# Microcontroller.net
KiCad netlist of a schematic drawn in Altium Designer
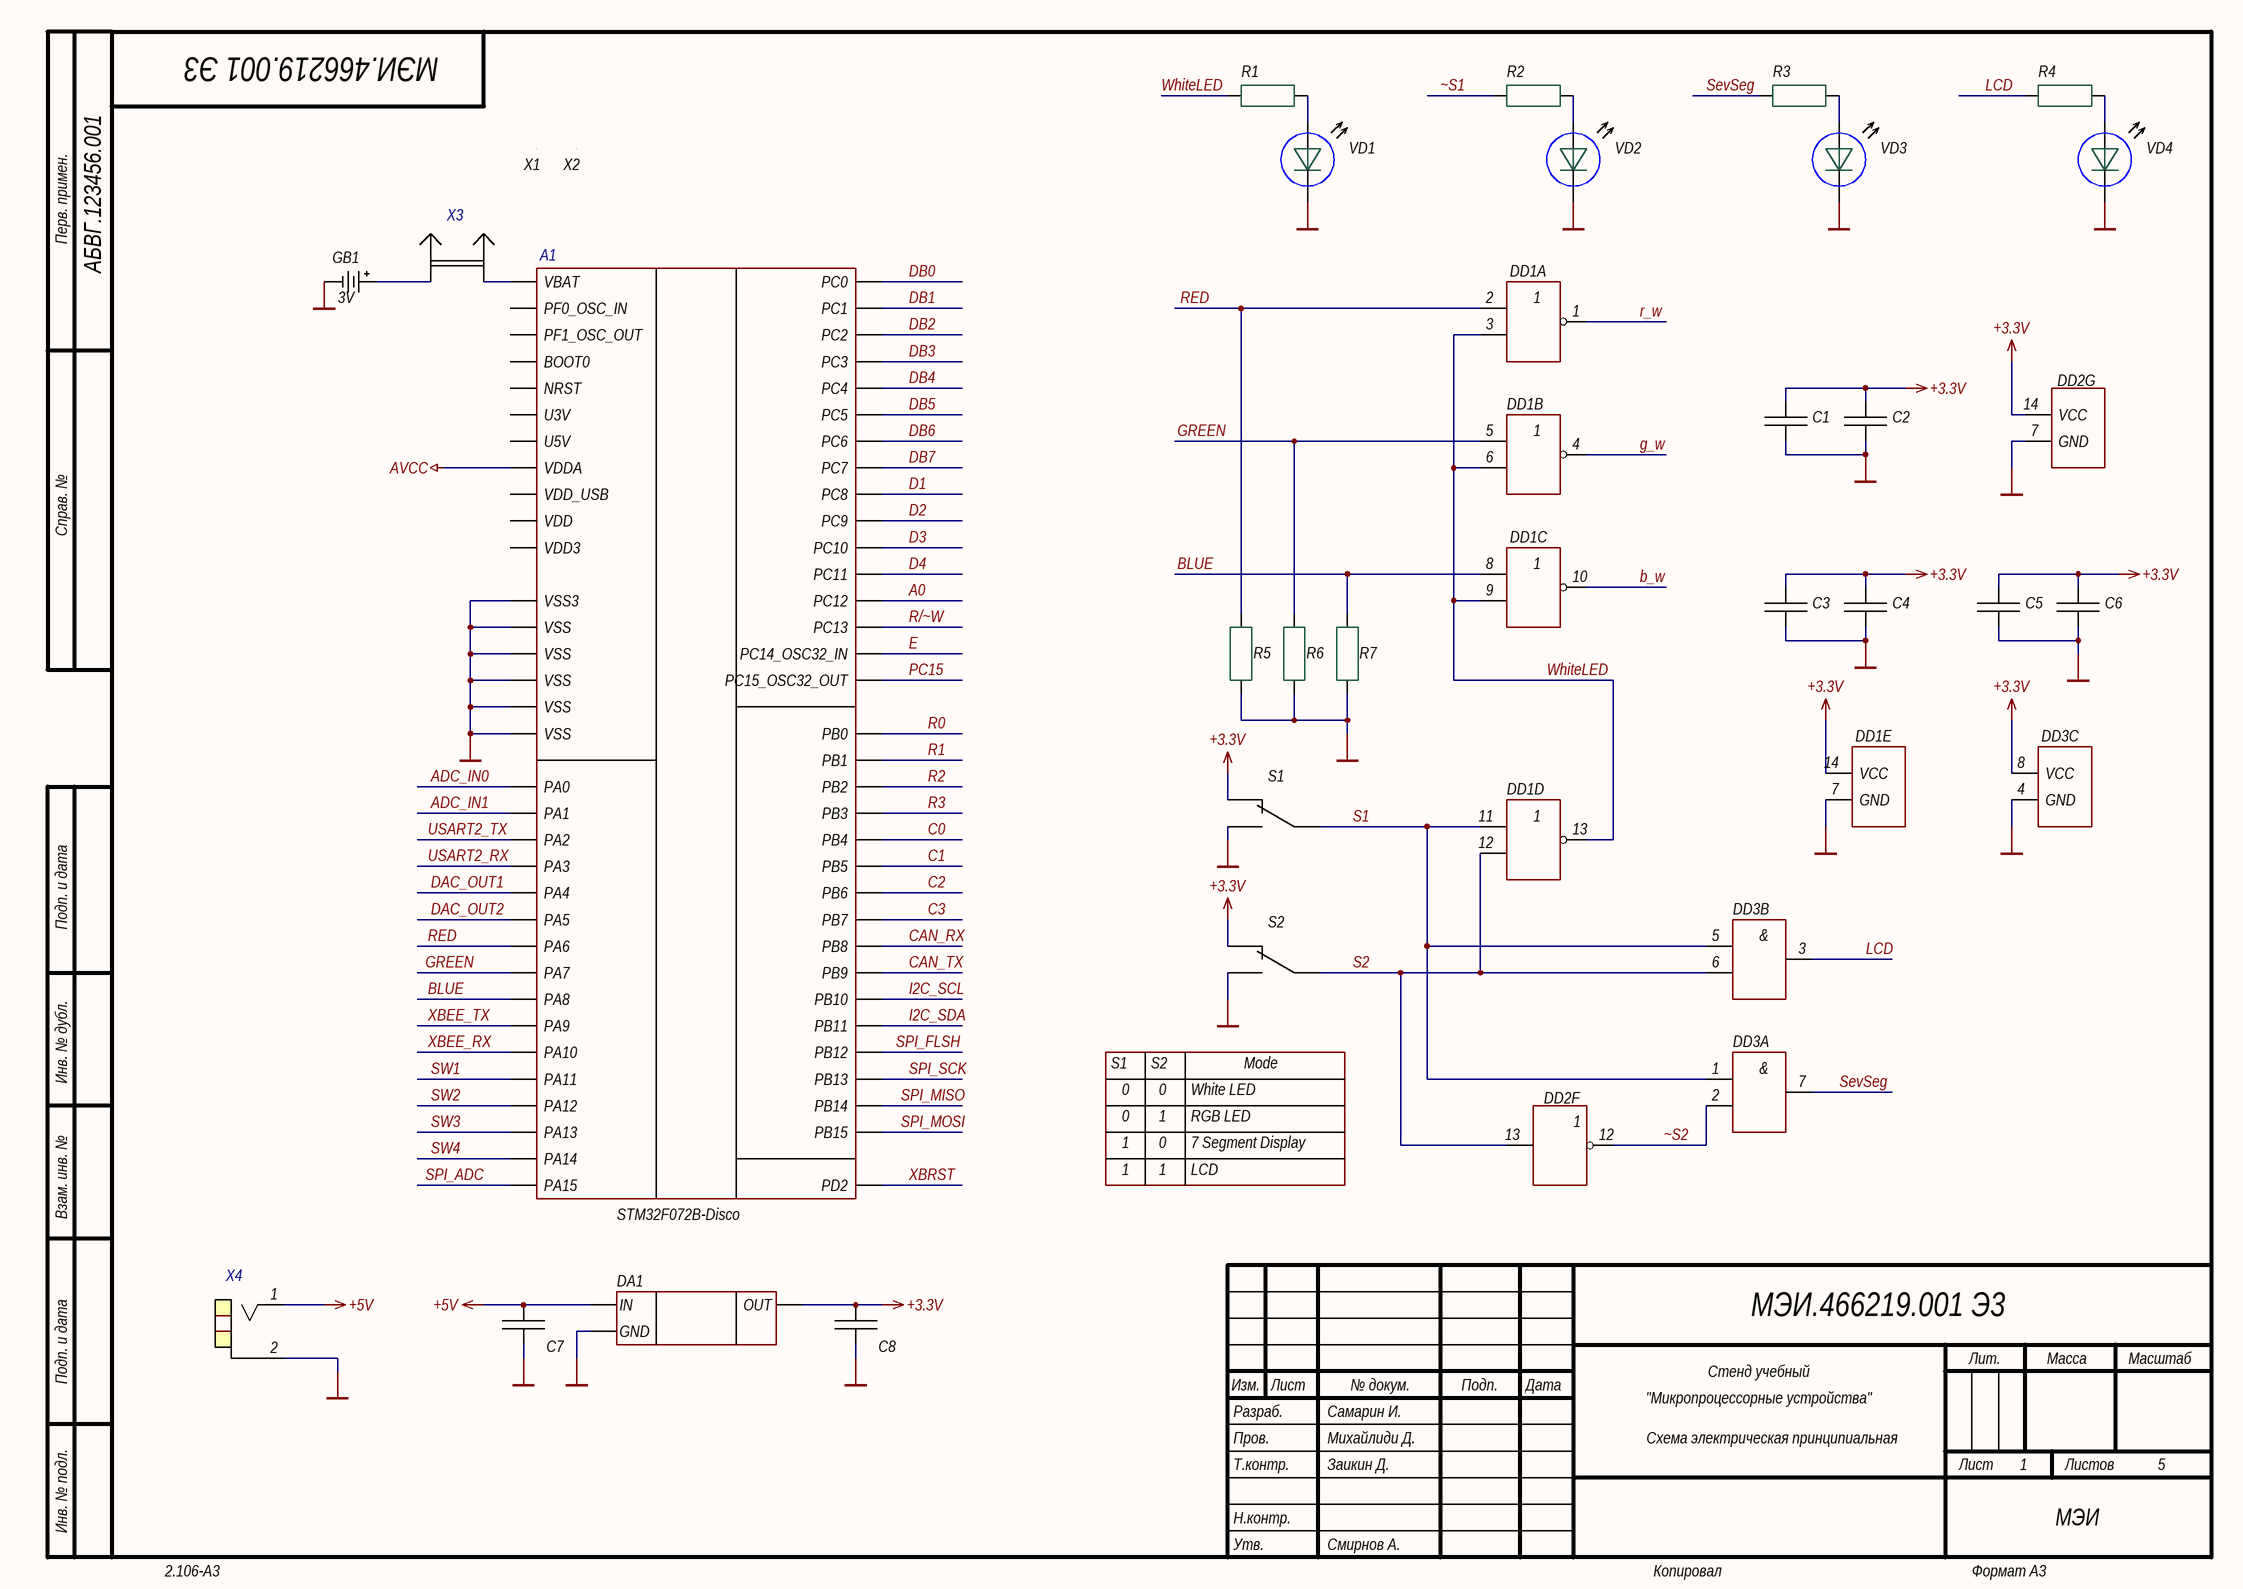
[diagram p0: Microcontroller.SchDoc]

(export (version "E")
  (design (tool "Eeschema 10.0.6"))
  (components
    (comp (ref "A1")
      (value "STM32F072B-Disco")
      (footprint "LeSta:STM32F072B-Disco")
      (description "The STM32F072 discovery kit")
      (fields (field (name "MODEL") "STM32F072B-Disco"))
      (libsource (lib "LeSta") (part "STM32F072B-Disco"))
    )
    (comp (ref "C1")
      (value "approved sub OK")
      (footprint "CAPC1608X90N")
      (description "Capacitor SMD Cer 100nF 10% 50V X7R 0603")
      (fields (field (name "TOLERANCE") "±10%"))
      (libsource (lib "PBL - Capacitors") (part "CAPC_100n_0603_X7R_50V_10%"))
    )
    (comp (ref "C2")
      (value "approved sub OK")
      (footprint "PBL - SMD Packages:CAPC1608X90N")
      (description "Capacitor SMD Cer 10uF 10% 10V X5R 0603")
      (fields (field (name "TOLERANCE") "±10%"))
      (libsource (lib "PBL - Capacitors") (part "CAPC_10u_0805_10V"))
    )
    (comp (ref "C3")
      (value "approved sub OK")
      (footprint "CAPC1608X90N")
      (description "Capacitor SMD Cer 100nF 10% 50V X7R 0603")
      (fields (field (name "TOLERANCE") "±10%"))
      (libsource (lib "PBL - Capacitors") (part "CAPC_100n_0603_X7R_50V_10%"))
    )
    (comp (ref "C4")
      (value "approved sub OK")
      (footprint "PBL - SMD Packages:CAPC1608X90N")
      (description "Capacitor SMD Cer 10uF 10% 10V X5R 0603")
      (fields (field (name "TOLERANCE") "±10%"))
      (libsource (lib "PBL - Capacitors") (part "CAPC_10u_0805_10V"))
    )
    (comp (ref "C5")
      (value "approved sub OK")
      (footprint "CAPC1608X90N")
      (description "Capacitor SMD Cer 100nF 10% 50V X7R 0603")
      (fields (field (name "TOLERANCE") "±10%"))
      (libsource (lib "PBL - Capacitors") (part "CAPC_100n_0603_X7R_50V_10%"))
    )
    (comp (ref "C6")
      (value "approved sub OK")
      (footprint "PBL - SMD Packages:CAPC1608X90N")
      (description "Capacitor SMD Cer 10uF 10% 10V X5R 0603")
      (fields (field (name "TOLERANCE") "±10%"))
      (libsource (lib "PBL - Capacitors") (part "CAPC_10u_0805_10V"))
    )
    (comp (ref "C7")
      (value "approved sub OK")
      (footprint "CAPC1608X90N")
      (description "Capacitor SMD Cer 1uF 10% 16V X7R 0603")
      (fields (field (name "TOLERANCE") "±10%"))
      (libsource (lib "PBL - Capacitors") (part "CAPC_1u_0603_X7R_16V_10%"))
    )
    (comp (ref "C8")
      (value "approved sub OK")
      (footprint "CAPC1608X90N")
      (description "Capacitor SMD Cer 1uF 10% 16V X7R 0603")
      (fields (field (name "TOLERANCE") "±10%"))
      (libsource (lib "PBL - Capacitors") (part "CAPC_1u_0603_X7R_16V_10%"))
    )
    (comp (ref "DA1")
      (value "ADP3339AKCZ-3.3-RL7")
      (footprint "PBL - SMD Packages:SOT223")
      (description "StateVoltageSource")
      (libsource (lib "LeSta") (part "ADP3339AKCZ-3.3-RL7"))
    )
    (comp (ref "DD1")
      (value "74LV02D.112")
      (footprint "PBL - SMD Packages:SOIC127P600X175-14AN")
      (description "4x2ИЛИ-НЕ")
      (libsource (lib "LeSta") (part "74LV02D.112"))
    )
    (comp (ref "DD2")
      (value "SN74AHCU04DR")
      (footprint "PBL - SMD Packages:SOIC127P780X200-14N")
      (description "HEX invertor")
      (libsource (lib "LeSta") (part "SN74AHCU04"))
    )
    (comp (ref "DD3")
      (value "74LVC2G08DP.125")
      (footprint "PBL - SMD Packages:TSSOP65P400X110-8N")
      (description "2x2И")
      (libsource (lib "LeSta") (part "74LVC2G08DP.125"))
    )
    (comp (ref "GB1")
      (value "3V")
      (footprint "LeSta:HU2032-1")
      (description "Holder")
      (libsource (lib "LeSta") (part "Battery"))
    )
    (comp (ref "R1")
      (value "Thick Film")
      (footprint "RESC1608X55N")
      (description "Resistor SMD chip 68 Ohm 0.1W 5% 0603")
      (fields (field (name "TOLERANCE") "±1%"))
      (libsource (lib "PBL - Resistors") (part "RES_68R_0603_5%"))
    )
    (comp (ref "R2")
      (value "Thick Film")
      (footprint "RESC1608X55N")
      (description "Resistor SMD chip 68 Ohm 0.1W 5% 0603")
      (fields (field (name "TOLERANCE") "±1%"))
      (libsource (lib "PBL - Resistors") (part "RES_68R_0603_5%"))
    )
    (comp (ref "R3")
      (value "Thick Film")
      (footprint "RESC1608X55N")
      (description "Resistor SMD chip 68 Ohm 0.1W 5% 0603")
      (fields (field (name "TOLERANCE") "±1%"))
      (libsource (lib "PBL - Resistors") (part "RES_68R_0603_5%"))
    )
    (comp (ref "R4")
      (value "Thick Film")
      (footprint "RESC1608X55N")
      (description "Resistor SMD chip 68 Ohm 0.1W 5% 0603")
      (fields (field (name "TOLERANCE") "±1%"))
      (libsource (lib "PBL - Resistors") (part "RES_68R_0603_5%"))
    )
    (comp (ref "R5")
      (value "Thick Film")
      (footprint "RESC1608X55N")
      (description "Resistor SMD chip 10k Ohm 0.1W 1% 0603")
      (fields (field (name "TOLERANCE") "±1%"))
      (libsource (lib "PBL - Resistors") (part "RES_10K_0603_1%"))
    )
    (comp (ref "R6")
      (value "Thick Film")
      (footprint "RESC1608X55N")
      (description "Resistor SMD chip 10k Ohm 0.1W 1% 0603")
      (fields (field (name "TOLERANCE") "±1%"))
      (libsource (lib "PBL - Resistors") (part "RES_10K_0603_1%"))
    )
    (comp (ref "R7")
      (value "Thick Film")
      (footprint "RESC1608X55N")
      (description "Resistor SMD chip 10k Ohm 0.1W 1% 0603")
      (fields (field (name "TOLERANCE") "±1%"))
      (libsource (lib "PBL - Resistors") (part "RES_10K_0603_1%"))
    )
    (comp (ref "S1")
      (value "ON-ON")
      (footprint "SWITCH_SPDT_SLIDER")
      (description "Switch THD vertical toggle SPDT")
      (libsource (lib "PBL - Switches") (part "SW_THD_SPDT_On-On"))
    )
    (comp (ref "S2")
      (value "ON-ON")
      (footprint "SWITCH_SPDT_SLIDER")
      (description "Switch THD vertical toggle SPDT")
      (libsource (lib "PBL - Switches") (part "SW_THD_SPDT_On-On"))
    )
    (comp (ref "VD1")
      (value "FYLS-0603URC")
      (footprint "PBL - SMD Packages:LED-0603-GREEN")
      (description "LED")
      (libsource (lib "LeSta") (part "FYLS-0603URC"))
    )
    (comp (ref "VD2")
      (value "FYLS-0603URC")
      (footprint "PBL - SMD Packages:LED-0603-GREEN")
      (description "LED")
      (libsource (lib "LeSta") (part "FYLS-0603URC"))
    )
    (comp (ref "VD3")
      (value "FYLS-0603URC")
      (footprint "PBL - SMD Packages:LED-0603-GREEN")
      (description "LED")
      (libsource (lib "LeSta") (part "FYLS-0603URC"))
    )
    (comp (ref "VD4")
      (value "FYLS-0603URC")
      (footprint "PBL - SMD Packages:LED-0603-GREEN")
      (description "LED")
      (libsource (lib "LeSta") (part "FYLS-0603URC"))
    )
    (comp (ref "X1")
      (value "PBS-40")
      (footprint "LeSta:PBS33")
      (description "CONN Disco")
      (libsource (lib "LeSta") (part "CONN Disco"))
    )
    (comp (ref "X2")
      (value "PBS-40")
      (footprint "LeSta:PBS33")
      (description "CONN Disco")
      (libsource (lib "LeSta") (part "CONN Disco"))
    )
    (comp (ref "X3")
      (value "PLS-2")
      (footprint "PBL - THD Packages:HDR_1x2")
      (description "Jumper")
      (libsource (lib "LeSta") (part "PLS-2 _1"))
    )
    (comp (ref "X4")
      (value "PJ-002A")
      (footprint "PBL - THD Packages:CONN_PWR_JACK_2.1x5.5mm")
      (description "Power connector")
      (libsource (lib "LeSta") (part "EJ503A (K375A)"))
    )
  )
  (nets
    (net (code "1") (name "+3.3V") (class "Default")
      (node (ref "C1") (pin "1") (pintype "passive"))
      (node (ref "C2") (pin "1") (pintype "passive"))
      (node (ref "C3") (pin "1") (pintype "passive"))
      (node (ref "C4") (pin "1") (pintype "passive"))
      (node (ref "C5") (pin "1") (pintype "passive"))
      (node (ref "C6") (pin "1") (pintype "passive"))
      (node (ref "C8") (pin "1") (pintype "passive"))
      (node (ref "DA1") (pin "2") (pinfunction "OUT_2") (pintype "passive"))
      (node (ref "DD1") (pin "14") (pinfunction "VCC_14") (pintype "passive"))
      (node (ref "DD2") (pin "14") (pinfunction "VCC_14") (pintype "passive"))
      (node (ref "DD3") (pin "8") (pinfunction "VCC_8") (pintype "passive"))
      (node (ref "S1") (pin "3") (pinfunction "3_3") (pintype "passive"))
      (node (ref "S2") (pin "3") (pinfunction "3_3") (pintype "passive"))
    )
    (net (code "2") (name "+5V") (class "Default")
      (node (ref "C7") (pin "1") (pintype "passive"))
      (node (ref "DA1") (pin "3") (pinfunction "IN_3") (pintype "passive"))
      (node (ref "X4") (pin "1") (pinfunction "VCC_1") (pintype "passive"))
    )
    (net (code "3") (name "/A0") (class "Default")
      (node (ref "A1") (pin "P2_13") (pinfunction "PC12_P2_13") (pintype "passive"))
    )
    (net (code "4") (name "/ADC_IN0") (class "Default")
      (node (ref "A1") (pin "P1_15") (pinfunction "PA0_P1_15") (pintype "passive"))
    )
    (net (code "5") (name "/ADC_IN1") (class "Default")
      (node (ref "A1") (pin "P1_16") (pinfunction "PA1_P1_16") (pintype "passive"))
    )
    (net (code "6") (name "/BLUE") (class "Default")
      (node (ref "A1") (pin "P2_25") (pinfunction "PA8_P2_25") (pintype "passive"))
      (node (ref "DD1") (pin "8") (pinfunction "3A_8") (pintype "passive"))
      (node (ref "R7") (pin "2") (pinfunction "2_2") (pintype "passive"))
    )
    (net (code "7") (name "/C0") (class "Default")
      (node (ref "A1") (pin "P2_10") (pinfunction "PB4_P2_10") (pintype "passive"))
    )
    (net (code "8") (name "/C1") (class "Default")
      (node (ref "A1") (pin "P2_9") (pinfunction "PB5_P2_9") (pintype "passive"))
    )
    (net (code "9") (name "/C2") (class "Default")
      (node (ref "A1") (pin "P2_8") (pinfunction "PB6_P2_8") (pintype "passive"))
    )
    (net (code "10") (name "/C3") (class "Default")
      (node (ref "A1") (pin "P2_7") (pinfunction "PB7_P2_7") (pintype "passive"))
    )
    (net (code "11") (name "/CAN_RX") (class "Default")
      (node (ref "A1") (pin "P2_4") (pinfunction "PB8_P2_4") (pintype "passive"))
    )
    (net (code "12") (name "/CAN_TX") (class "Default")
      (node (ref "A1") (pin "P2_3") (pinfunction "PB9_P2_3") (pintype "passive"))
    )
    (net (code "13") (name "/D1") (class "Default")
      (node (ref "A1") (pin "P2_27") (pinfunction "PC8_P2_27") (pintype "passive"))
    )
    (net (code "14") (name "/D2") (class "Default")
      (node (ref "A1") (pin "P2_26") (pinfunction "PC9_P2_26") (pintype "passive"))
    )
    (net (code "15") (name "/D3") (class "Default")
      (node (ref "A1") (pin "P2_15") (pinfunction "PC10_P2_15") (pintype "passive"))
    )
    (net (code "16") (name "/D4") (class "Default")
      (node (ref "A1") (pin "P2_14") (pinfunction "PC11_P2_14") (pintype "passive"))
    )
    (net (code "17") (name "/DAC_OUT1") (class "Default")
      (node (ref "A1") (pin "P1_21") (pinfunction "PA4_P1_21") (pintype "passive"))
    )
    (net (code "18") (name "/DAC_OUT2") (class "Default")
      (node (ref "A1") (pin "P1_22") (pinfunction "PA5_P1_22") (pintype "passive"))
    )
    (net (code "19") (name "/DB0") (class "Default")
      (node (ref "A1") (pin "P1_11") (pinfunction "PC0_P1_11") (pintype "passive"))
    )
    (net (code "20") (name "/DB1") (class "Default")
      (node (ref "A1") (pin "P1_12") (pinfunction "PC1_P1_12") (pintype "passive"))
    )
    (net (code "21") (name "/DB2") (class "Default")
      (node (ref "A1") (pin "P1_13") (pinfunction "PC2_P1_13") (pintype "passive"))
    )
    (net (code "22") (name "/DB3") (class "Default")
      (node (ref "A1") (pin "P1_14") (pinfunction "PC3_P1_14") (pintype "passive"))
    )
    (net (code "23") (name "/DB4") (class "Default")
      (node (ref "A1") (pin "P1_25") (pinfunction "PC4_P1_25") (pintype "passive"))
    )
    (net (code "24") (name "/DB5") (class "Default")
      (node (ref "A1") (pin "P1_26") (pinfunction "PC5_P1_26") (pintype "passive"))
    )
    (net (code "25") (name "/DB6") (class "Default")
      (node (ref "A1") (pin "P2_29") (pinfunction "PC6_P2_29") (pintype "passive"))
    )
    (net (code "26") (name "/DB7") (class "Default")
      (node (ref "A1") (pin "P2_28") (pinfunction "PC7_P2_28") (pintype "passive"))
    )
    (net (code "27") (name "/E") (class "Default")
      (node (ref "A1") (pin "P1_5") (pinfunction "PC14_OSC32_IN_P1_5") (pintype "passive"))
    )
    (net (code "28") (name "/GREEN") (class "Default")
      (node (ref "A1") (pin "P1_24") (pinfunction "PA7_P1_24") (pintype "passive"))
      (node (ref "DD1") (pin "5") (pinfunction "2A_5") (pintype "passive"))
      (node (ref "R6") (pin "2") (pinfunction "2_2") (pintype "passive"))
    )
    (net (code "29") (name "/I2C_SCL") (class "Default")
      (node (ref "A1") (pin "P1_30") (pinfunction "PB10_P1_30") (pintype "passive"))
    )
    (net (code "30") (name "/I2C_SDA") (class "Default")
      (node (ref "A1") (pin "P1_31") (pinfunction "PB11_P1_31") (pintype "passive"))
    )
    (net (code "31") (name "/LCD") (class "Default")
      (node (ref "DD3") (pin "3") (pinfunction "2Y_3") (pintype "passive"))
      (node (ref "R4") (pin "1") (pinfunction "1_1") (pintype "passive"))
    )
    (net (code "32") (name "/PC15") (class "Default")
      (node (ref "A1") (pin "P1_6") (pinfunction "PC15_OSC32_OUT_P1_6") (pintype "passive"))
    )
    (net (code "33") (name "/R0") (class "Default")
      (node (ref "A1") (pin "P1_27") (pinfunction "PB0_P1_27") (pintype "passive"))
    )
    (net (code "34") (name "/R1") (class "Default")
      (node (ref "A1") (pin "P1_28") (pinfunction "PB1_P1_28") (pintype "passive"))
    )
    (net (code "35") (name "/R2") (class "Default")
      (node (ref "A1") (pin "P1_29") (pinfunction "PB2_P1_29") (pintype "passive"))
    )
    (net (code "36") (name "/R3") (class "Default")
      (node (ref "A1") (pin "P2_11") (pinfunction "PB3_P2_11") (pintype "passive"))
    )
    (net (code "37") (name "/RED") (class "Default")
      (node (ref "A1") (pin "P1_23") (pinfunction "PA6_P1_23") (pintype "passive"))
      (node (ref "DD1") (pin "2") (pinfunction "1A_2") (pintype "passive"))
      (node (ref "R5") (pin "2") (pinfunction "2_2") (pintype "passive"))
    )
    (net (code "38") (name "/R{slash}~W") (class "Default")
      (node (ref "A1") (pin "P1_4") (pinfunction "PC13_P1_4") (pintype "passive"))
    )
    (net (code "39") (name "/S1") (class "Default")
      (node (ref "DD1") (pin "11") (pinfunction "4A_11") (pintype "passive"))
      (node (ref "DD3") (pin "1") (pinfunction "1A_1") (pintype "passive"))
      (node (ref "DD3") (pin "5") (pinfunction "2A_5") (pintype "passive"))
      (node (ref "S1") (pin "2") (pinfunction "2_2") (pintype "passive"))
    )
    (net (code "40") (name "/S2") (class "Default")
      (node (ref "DD1") (pin "12") (pinfunction "4B_12") (pintype "passive"))
      (node (ref "DD2") (pin "13") (pinfunction "6A_13") (pintype "passive"))
      (node (ref "DD3") (pin "6") (pinfunction "2B_6") (pintype "passive"))
      (node (ref "S2") (pin "2") (pinfunction "2_2") (pintype "passive"))
    )
    (net (code "41") (name "/SPI_ADC") (class "Default")
      (node (ref "A1") (pin "P2_16") (pinfunction "PA15_P2_16") (pintype "passive"))
    )
    (net (code "42") (name "/SPI_FLSH") (class "Default")
      (node (ref "A1") (pin "P1_32") (pinfunction "PB12_P1_32") (pintype "passive"))
    )
    (net (code "43") (name "/SPI_MISO") (class "Default")
      (node (ref "A1") (pin "P2_31") (pinfunction "PB14_P2_31") (pintype "passive"))
    )
    (net (code "44") (name "/SPI_MOSI") (class "Default")
      (node (ref "A1") (pin "P2_30") (pinfunction "PB15_P2_30") (pintype "passive"))
    )
    (net (code "45") (name "/SPI_SCK") (class "Default")
      (node (ref "A1") (pin "P2_32") (pinfunction "PB13_P2_32") (pintype "passive"))
    )
    (net (code "46") (name "/SW1") (class "Default")
      (node (ref "A1") (pin "P2_22") (pinfunction "PA11_P2_22") (pintype "passive"))
    )
    (net (code "47") (name "/SW2") (class "Default")
      (node (ref "A1") (pin "P2_21") (pinfunction "PA12_P2_21") (pintype "passive"))
    )
    (net (code "48") (name "/SW3") (class "Default")
      (node (ref "A1") (pin "P2_20") (pinfunction "PA13_P2_20") (pintype "passive"))
    )
    (net (code "49") (name "/SW4") (class "Default")
      (node (ref "A1") (pin "P2_17") (pinfunction "PA14_P2_17") (pintype "passive"))
    )
    (net (code "50") (name "/SevSeg") (class "Default")
      (node (ref "DD3") (pin "7") (pinfunction "1Y_7") (pintype "passive"))
      (node (ref "R3") (pin "1") (pinfunction "1_1") (pintype "passive"))
    )
    (net (code "51") (name "/USART2_RX") (class "Default")
      (node (ref "A1") (pin "P1_18") (pinfunction "PA3_P1_18") (pintype "passive"))
    )
    (net (code "52") (name "/USART2_TX") (class "Default")
      (node (ref "A1") (pin "P1_17") (pinfunction "PA2_P1_17") (pintype "passive"))
    )
    (net (code "53") (name "/WhiteLED") (class "Default")
      (node (ref "DD1") (pin "13") (pinfunction "4Y_13") (pintype "passive"))
      (node (ref "DD1") (pin "3") (pinfunction "1B_3") (pintype "passive"))
      (node (ref "DD1") (pin "6") (pinfunction "2A_6") (pintype "passive"))
      (node (ref "DD1") (pin "9") (pinfunction "3B_9") (pintype "passive"))
      (node (ref "R1") (pin "1") (pinfunction "1_1") (pintype "passive"))
    )
    (net (code "54") (name "/XBEE_RX") (class "Default")
      (node (ref "A1") (pin "P2_23") (pinfunction "PA10_P2_23") (pintype "passive"))
    )
    (net (code "55") (name "/XBEE_TX") (class "Default")
      (node (ref "A1") (pin "P2_24") (pinfunction "PA9_P2_24") (pintype "passive"))
    )
    (net (code "56") (name "/XBRST") (class "Default")
      (node (ref "A1") (pin "P2_12") (pinfunction "PD2_P2_12") (pintype "passive"))
    )
    (net (code "57") (name "/b_w") (class "Default")
      (node (ref "DD1") (pin "10") (pinfunction "3Y_10") (pintype "passive"))
    )
    (net (code "58") (name "/g_w") (class "Default")
      (node (ref "DD1") (pin "4") (pinfunction "2Y_4") (pintype "passive"))
    )
    (net (code "59") (name "/r_w") (class "Default")
      (node (ref "DD1") (pin "1") (pinfunction "1Y_1") (pintype "passive"))
    )
    (net (code "60") (name "/~S1") (class "Default")
      (node (ref "R2") (pin "1") (pinfunction "1_1") (pintype "passive"))
    )
    (net (code "61") (name "/~S2") (class "Default")
      (node (ref "DD2") (pin "12") (pinfunction "6Y_12") (pintype "passive"))
      (node (ref "DD3") (pin "2") (pinfunction "1B_2") (pintype "passive"))
    )
    (net (code "62") (name "AVCC") (class "Default")
      (node (ref "A1") (pin "P2_19") (pinfunction "VDDA_P2_19") (pintype "passive"))
    )
    (net (code "63") (name "GND") (class "Default")
      (node (ref "A1") (pin "P1_19") (pinfunction "VSS3_P1_19") (pintype "passive"))
      (node (ref "A1") (pin "P1_2") (pinfunction "VSS_P1_2") (pintype "passive"))
      (node (ref "A1") (pin "P1_33") (pinfunction "VSS_P1_33") (pintype "passive"))
      (node (ref "A1") (pin "P1_9") (pinfunction "VSS_P1_9") (pintype "passive"))
      (node (ref "A1") (pin "P2_2") (pinfunction "VSS_P2_2") (pintype "passive"))
      (node (ref "A1") (pin "P2_33") (pinfunction "VSS_P2_33") (pintype "passive"))
      (node (ref "C1") (pin "2") (pintype "passive"))
      (node (ref "C2") (pin "2") (pintype "passive"))
      (node (ref "C3") (pin "2") (pintype "passive"))
      (node (ref "C4") (pin "2") (pintype "passive"))
      (node (ref "C5") (pin "2") (pintype "passive"))
      (node (ref "C6") (pin "2") (pintype "passive"))
      (node (ref "C7") (pin "2") (pintype "passive"))
      (node (ref "C8") (pin "2") (pintype "passive"))
      (node (ref "DA1") (pin "1") (pinfunction "GND_1") (pintype "passive"))
      (node (ref "DD1") (pin "7") (pinfunction "GND_7") (pintype "passive"))
      (node (ref "DD2") (pin "7") (pinfunction "GND_7") (pintype "passive"))
      (node (ref "DD3") (pin "4") (pinfunction "GND_4") (pintype "passive"))
      (node (ref "GB1") (pin "GND") (pinfunction "MINUS_GND") (pintype "passive"))
      (node (ref "R5") (pin "1") (pinfunction "1_1") (pintype "passive"))
      (node (ref "R6") (pin "1") (pinfunction "1_1") (pintype "passive"))
      (node (ref "R7") (pin "1") (pinfunction "1_1") (pintype "passive"))
      (node (ref "S1") (pin "1") (pinfunction "1_1") (pintype "passive"))
      (node (ref "S2") (pin "1") (pinfunction "1_1") (pintype "passive"))
      (node (ref "VD1") (pin "K") (pinfunction "K_K") (pintype "passive"))
      (node (ref "VD2") (pin "K") (pinfunction "K_K") (pintype "passive"))
      (node (ref "VD3") (pin "K") (pinfunction "K_K") (pintype "passive"))
      (node (ref "VD4") (pin "K") (pinfunction "K_K") (pintype "passive"))
      (node (ref "X4") (pin "2") (pinfunction "GND_2") (pintype "passive"))
    )
    (net (code "64") (name "Net-(A1-VBAT)") (class "Default")
      (node (ref "A1") (pin "P1_3") (pinfunction "VBAT_P1_3") (pintype "passive"))
      (node (ref "X3") (pin "2") (pinfunction "*_2") (pintype "passive"))
    )
    (net (code "65") (name "Net-(GB1-PLUS)") (class "Default")
      (node (ref "GB1") (pin "VCC") (pinfunction "PLUS_VCC") (pintype "passive"))
      (node (ref "X3") (pin "1") (pinfunction "*_1") (pintype "passive"))
    )
    (net (code "66") (name "Net-(VD1-AR)") (class "Default")
      (node (ref "R1") (pin "2") (pinfunction "2_2") (pintype "passive"))
      (node (ref "VD1") (pin "A") (pinfunction "AR_A") (pintype "passive"))
    )
    (net (code "67") (name "Net-(VD2-AR)") (class "Default")
      (node (ref "R2") (pin "2") (pinfunction "2_2") (pintype "passive"))
      (node (ref "VD2") (pin "A") (pinfunction "AR_A") (pintype "passive"))
    )
    (net (code "68") (name "Net-(VD3-AR)") (class "Default")
      (node (ref "R3") (pin "2") (pinfunction "2_2") (pintype "passive"))
      (node (ref "VD3") (pin "A") (pinfunction "AR_A") (pintype "passive"))
    )
    (net (code "69") (name "Net-(VD4-AR)") (class "Default")
      (node (ref "R4") (pin "2") (pinfunction "2_2") (pintype "passive"))
      (node (ref "VD4") (pin "A") (pinfunction "AR_A") (pintype "passive"))
    )
    (net (code "70") (name "unconnected-(A1-BOOT0-PadP2_6)") (class "Default")
      (node (ref "A1") (pin "P2_6") (pinfunction "BOOT0_P2_6") (pintype "passive"))
    )
    (net (code "71") (name "unconnected-(A1-NRST-PadP1_10)") (class "Default")
      (node (ref "A1") (pin "P1_10") (pinfunction "NRST_P1_10") (pintype "passive"))
    )
    (net (code "72") (name "unconnected-(A1-PF0_OSC_IN-PadP1_7)") (class "Default")
      (node (ref "A1") (pin "P1_7") (pinfunction "PF0_OSC_IN_P1_7") (pintype "passive"))
    )
    (net (code "73") (name "unconnected-(A1-PF1_OSC_OUT-PadP1_8)") (class "Default")
      (node (ref "A1") (pin "P1_8") (pinfunction "PF1_OSC_OUT_P1_8") (pintype "passive"))
    )
    (net (code "74") (name "unconnected-(A1-U3V-PadP1_1)") (class "Default")
      (node (ref "A1") (pin "P1_1") (pinfunction "U3V_P1_1") (pintype "passive"))
    )
    (net (code "75") (name "unconnected-(A1-U5V-PadP2_1)") (class "Default")
      (node (ref "A1") (pin "P2_1") (pinfunction "U5V_P2_1") (pintype "passive"))
    )
    (net (code "76") (name "unconnected-(A1-VDD-PadP2_5)") (class "Default")
      (node (ref "A1") (pin "P2_5") (pinfunction "VDD_P2_5") (pintype "passive"))
    )
    (net (code "77") (name "unconnected-(A1-VDD3-PadP1_20)") (class "Default")
      (node (ref "A1") (pin "P1_20") (pinfunction "VDD3_P1_20") (pintype "passive"))
    )
    (net (code "78") (name "unconnected-(A1-VDD_USB-PadP2_18)") (class "Default")
      (node (ref "A1") (pin "P2_18") (pinfunction "VDD_USB_P2_18") (pintype "passive"))
    )
    (net (code "79") (name "unconnected-(X1-VCC-Pad1)") (class "Default")
      (node (ref "X1") (pin "1") (pinfunction "VCC_1") (pintype "passive"))
    )
    (net (code "80") (name "unconnected-(X2-VCC-Pad1)") (class "Default")
      (node (ref "X2") (pin "1") (pinfunction "VCC_1") (pintype "passive"))
    )
  )
)
